# 02_Power_Control.net
KiCad netlist of a schematic drawn in Altium Designer
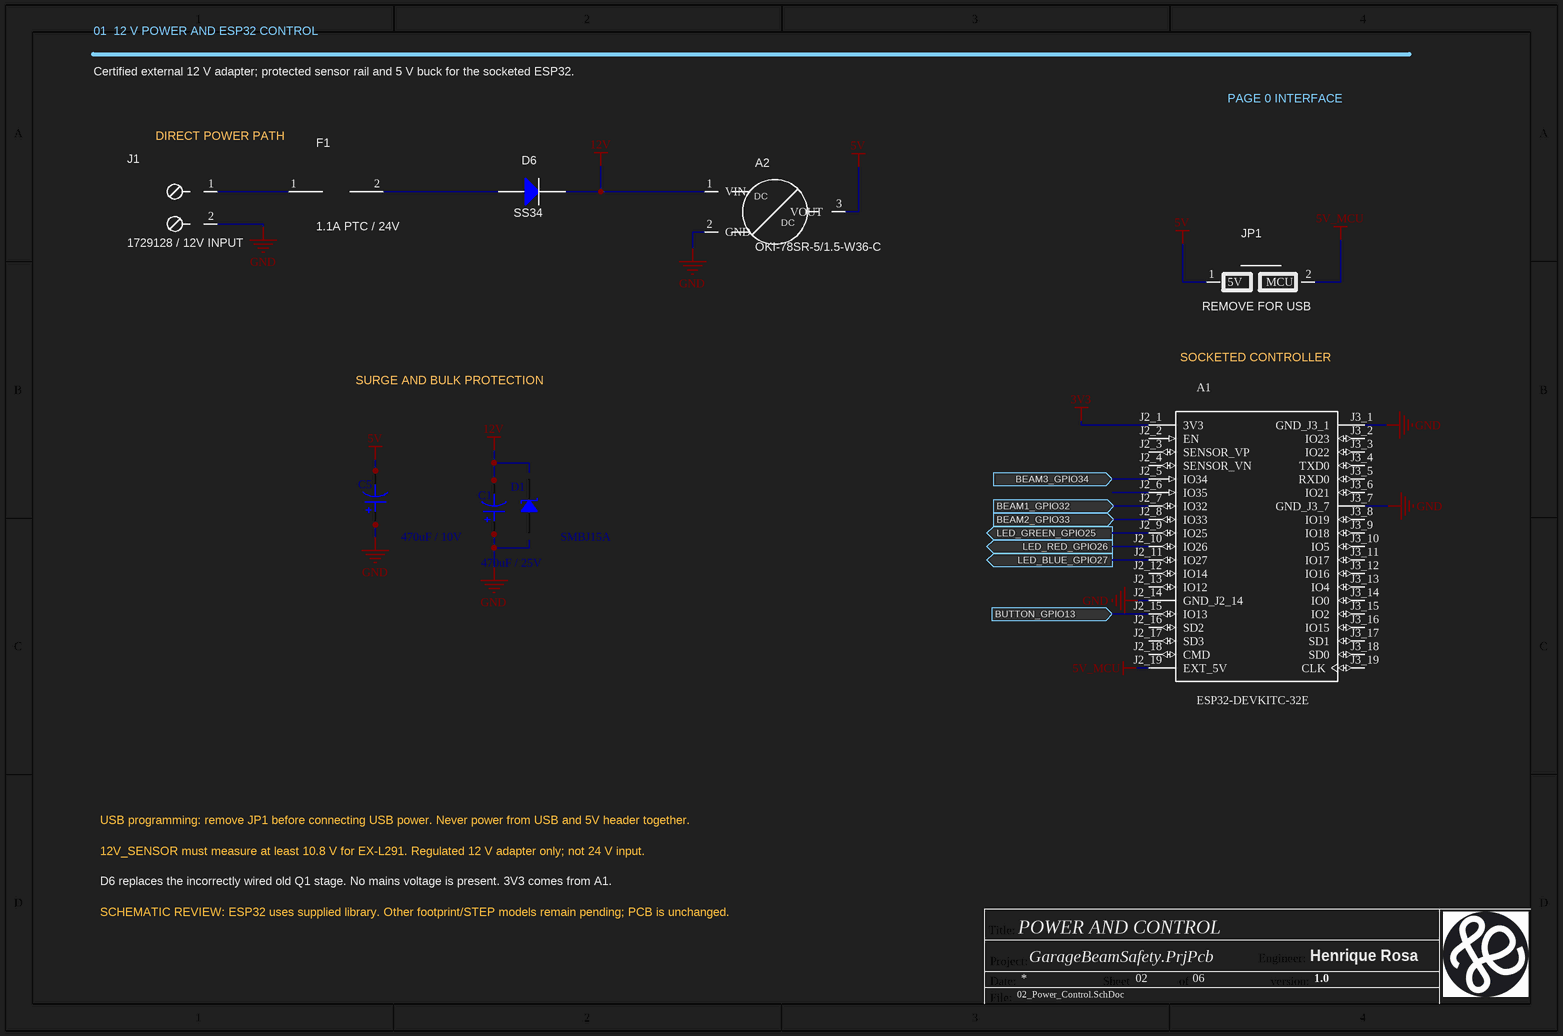
[diagram p0: 02_Power_Control.SchDoc]

(export (version "E")
  (design (tool "Eeschema 10.0.6"))
  (components
    (comp (ref "A1")
      (value "ESP32-DEVKITC-32E")
      (footprint "MODULE_ESP32-DEVKITC-32E:MODULE_ESP32-DEVKITC-32E")
      (fields
        (field (name "MF") "Espressif Systems")
        (field (name "MANUFACTURER PART NUMBER") "ESP32-DevKitC-32E")
      )
      (libsource (lib "ReviewedComponents_20260912-233454") (part "ESP32-DevKitC-32E__A1_view"))
    )
    (comp (ref "A2")
      (value "OKI-78SR-5/1.5-W36-C")
      (footprint "PartSpecificFootprints:MURATA_OKI78SR_VERTICAL")
      (description "12 V to regulated 5 V DC/DC module")
      (fields (field (name "MANUFACTURER") "Murata"))
      (libsource (lib "ReviewedComponents_20260912-233454") (part "OKI-78SR-5_1_5-W36-C__A2_view"))
    )
    (comp (ref "C1")
      (value "470uF / 25V")
      (footprint "PinRepairFootprints:PANASONIC_EEUFR1E471_D10_P5")
      (description "SMT Polarised Capacitor")
      (fields (field (name "PART NUMBER") "EEU-FR1E471") (field (name "MANUFACTURER") "Panasonic"))
      (libsource (lib "SCH - PASSIVES - POLARISED CAPACITOR") (part "Polarised Capacitor"))
    )
    (comp (ref "C5")
      (value "470uF / 10V")
      (footprint "PinRepairFootprints:PANASONIC_EEUFR1A471_D8_P3_5")
      (description "SMT Polarised Capacitor")
      (fields (field (name "PART NUMBER") "EEU-FR1A471") (field (name "MANUFACTURER") "Panasonic"))
      (libsource (lib "SCH - PASSIVES - POLARISED CAPACITOR") (part "Polarised Capacitor"))
    )
    (comp (ref "D1")
      (value "SMBJ15A")
      (footprint "PinRepairFootprints:SMBJ15A_A1_K2")
      (description "Rectifier Diode")
      (fields (field (name "MANUFACTURER") "Littelfuse"))
      (libsource (lib "SCH - DIODES - DIODE TVS UNI") (part "DIODE TVS UNI"))
    )
    (comp (ref "D6")
      (value "SS34")
      (footprint "PinRepairFootprints:SS34_A1_K2")
      (description "Series reverse-polarity Schottky diode")
      (fields (field (name "PART NUMBER") "SS34-E3/57T") (field (name "MANUFACTURER") "Vishay"))
      (libsource (lib "ReviewedComponents_20260912-233454") (part "SS34-E3_57T__D6_view"))
    )
    (comp (ref "F1")
      (value "1.1A PTC / 24V")
      (footprint "PinRepairFootprints:BOURNS_MFMSMF110_24X_STYLE2")
      (description "Resettable 12 V input fuse")
      (fields
        (field (name "MANUFACTURER") "Bourns")
        (field (name "MANUFACTURER PART NUMBER") "MF-MSMF110/24X-2")
      )
      (libsource (lib "ReviewedComponents_20260912-233454") (part "MF-MSMF110_24X-2__F1_view"))
    )
    (comp (ref "J1")
      (value "1729128 / 12V INPUT")
      (footprint "PartSpecificFootprints:PHOENIX_1729128_MKDSN_2_508")
      (description "Two-position 5.08 mm screw terminal")
      (fields
        (field (name "MANUFACTURER") "Phoenix Contact")
        (field (name "MANUFACTURER PART NUMBER") "1729128")
      )
      (libsource (lib "ReviewedComponents_20260912-233454") (part "1729128__J1_view"))
    )
    (comp (ref "JP1")
      (value "REMOVE FOR USB")
      (footprint "PinRepairFootprints:SAMTEC_TSW102_07_SINGLE")
      (description "External 5 V disconnect; fit shunt only without USB")
      (fields
        (field (name "MANUFACTURER") "Samtec")
        (field (name "MANUFACTURER PART NUMBER") "TSW-102-07-G-S")
      )
      (libsource (lib "ReviewedComponents_20260912-233454") (part "TSW-102-07-G-S__JP1_view"))
    )
  )
  (nets
    (net (code "1") (name "/BEAM1_GPIO32") (class "Default")
      (node (ref "A1") (pin "J2_7") (pinfunction "IO32_J2_7") (pintype "bidirectional"))
    )
    (net (code "2") (name "/BEAM2_GPIO33") (class "Default")
      (node (ref "A1") (pin "J2_8") (pinfunction "IO33_J2_8") (pintype "bidirectional"))
    )
    (net (code "3") (name "/BEAM3_GPIO34") (class "Default")
      (node (ref "A1") (pin "J2_5") (pinfunction "IO34_J2_5") (pintype "input"))
    )
    (net (code "4") (name "/BUTTON_GPIO13") (class "Default")
      (node (ref "A1") (pin "J2_15") (pinfunction "IO13_J2_15") (pintype "bidirectional"))
    )
    (net (code "5") (name "/LED_BLUE_GPIO27") (class "Default")
      (node (ref "A1") (pin "J2_11") (pinfunction "IO27_J2_11") (pintype "bidirectional"))
    )
    (net (code "6") (name "/LED_GREEN_GPIO25") (class "Default")
      (node (ref "A1") (pin "J2_9") (pinfunction "IO25_J2_9") (pintype "bidirectional"))
    )
    (net (code "7") (name "/LED_RED_GPIO26") (class "Default")
      (node (ref "A1") (pin "J2_10") (pinfunction "IO26_J2_10") (pintype "bidirectional"))
    )
    (net (code "8") (name "3V3") (class "Default")
      (node (ref "A1") (pin "J2_1") (pinfunction "3V3_J2_1") (pintype "power_in"))
    )
    (net (code "9") (name "5V") (class "Default")
      (node (ref "A2") (pin "3") (pinfunction "VOUT_3") (pintype "passive"))
      (node (ref "C5") (pin "2") (pinfunction "2_2") (pintype "passive"))
      (node (ref "JP1") (pin "1") (pinfunction "5V_1") (pintype "passive"))
    )
    (net (code "10") (name "5V_MCU") (class "Default")
      (node (ref "A1") (pin "J2_19") (pinfunction "EXT_5V_J2_19") (pintype "power_in"))
      (node (ref "JP1") (pin "2") (pinfunction "MCU_2") (pintype "passive"))
    )
    (net (code "11") (name "12V") (class "Default")
      (node (ref "A2") (pin "1") (pinfunction "VIN_1") (pintype "passive"))
      (node (ref "C1") (pin "2") (pinfunction "2_2") (pintype "passive"))
      (node (ref "D6") (pin "2") (pinfunction "K_2") (pintype "passive"))
    )
    (net (code "12") (name "GND") (class "Default")
      (node (ref "A1") (pin "J2_14") (pinfunction "GND_J2_14_J2_14") (pintype "power_in"))
      (node (ref "A1") (pin "J3_1") (pinfunction "GND_J3_1_J3_1") (pintype "power_in"))
      (node (ref "A1") (pin "J3_7") (pinfunction "GND_J3_7_J3_7") (pintype "power_in"))
      (node (ref "A2") (pin "2") (pinfunction "GND_2") (pintype "passive"))
      (node (ref "C1") (pin "1") (pinfunction "1_1") (pintype "passive"))
      (node (ref "C5") (pin "1") (pinfunction "1_1") (pintype "passive"))
      (node (ref "J1") (pin "2") (pinfunction "0V_2") (pintype "power_in"))
    )
    (net (code "13") (name "Net-(D6-A)") (class "Default")
      (node (ref "D6") (pin "1") (pinfunction "A_1") (pintype "passive"))
      (node (ref "F1") (pin "2") (pintype "passive"))
    )
    (net (code "14") (name "Net-(J1-+12V)") (class "Default")
      (node (ref "F1") (pin "1") (pintype "passive"))
      (node (ref "J1") (pin "1") (pinfunction "+12V_1") (pintype "power_in"))
    )
    (net (code "15") (name "unconnected-(A1-CLK-PadJ3_19)") (class "Default")
      (node (ref "A1") (pin "J3_19") (pinfunction "CLK_J3_19") (pintype "bidirectional"))
    )
    (net (code "16") (name "unconnected-(A1-CMD-PadJ2_18)") (class "Default")
      (node (ref "A1") (pin "J2_18") (pinfunction "CMD_J2_18") (pintype "bidirectional"))
    )
    (net (code "17") (name "unconnected-(A1-EN-PadJ2_2)") (class "Default")
      (node (ref "A1") (pin "J2_2") (pinfunction "EN_J2_2") (pintype "input"))
    )
    (net (code "18") (name "unconnected-(A1-IO0-PadJ3_14)") (class "Default")
      (node (ref "A1") (pin "J3_14") (pinfunction "IO0_J3_14") (pintype "bidirectional"))
    )
    (net (code "19") (name "unconnected-(A1-IO2-PadJ3_15)") (class "Default")
      (node (ref "A1") (pin "J3_15") (pinfunction "IO2_J3_15") (pintype "bidirectional"))
    )
    (net (code "20") (name "unconnected-(A1-IO4-PadJ3_13)") (class "Default")
      (node (ref "A1") (pin "J3_13") (pinfunction "IO4_J3_13") (pintype "bidirectional"))
    )
    (net (code "21") (name "unconnected-(A1-IO5-PadJ3_10)") (class "Default")
      (node (ref "A1") (pin "J3_10") (pinfunction "IO5_J3_10") (pintype "bidirectional"))
    )
    (net (code "22") (name "unconnected-(A1-IO12-PadJ2_13)") (class "Default")
      (node (ref "A1") (pin "J2_13") (pinfunction "IO12_J2_13") (pintype "bidirectional"))
    )
    (net (code "23") (name "unconnected-(A1-IO14-PadJ2_12)") (class "Default")
      (node (ref "A1") (pin "J2_12") (pinfunction "IO14_J2_12") (pintype "bidirectional"))
    )
    (net (code "24") (name "unconnected-(A1-IO15-PadJ3_16)") (class "Default")
      (node (ref "A1") (pin "J3_16") (pinfunction "IO15_J3_16") (pintype "bidirectional"))
    )
    (net (code "25") (name "unconnected-(A1-IO16-PadJ3_12)") (class "Default")
      (node (ref "A1") (pin "J3_12") (pinfunction "IO16_J3_12") (pintype "bidirectional"))
    )
    (net (code "26") (name "unconnected-(A1-IO17-PadJ3_11)") (class "Default")
      (node (ref "A1") (pin "J3_11") (pinfunction "IO17_J3_11") (pintype "bidirectional"))
    )
    (net (code "27") (name "unconnected-(A1-IO18-PadJ3_9)") (class "Default")
      (node (ref "A1") (pin "J3_9") (pinfunction "IO18_J3_9") (pintype "bidirectional"))
    )
    (net (code "28") (name "unconnected-(A1-IO19-PadJ3_8)") (class "Default")
      (node (ref "A1") (pin "J3_8") (pinfunction "IO19_J3_8") (pintype "bidirectional"))
    )
    (net (code "29") (name "unconnected-(A1-IO21-PadJ3_6)") (class "Default")
      (node (ref "A1") (pin "J3_6") (pinfunction "IO21_J3_6") (pintype "bidirectional"))
    )
    (net (code "30") (name "unconnected-(A1-IO22-PadJ3_3)") (class "Default")
      (node (ref "A1") (pin "J3_3") (pinfunction "IO22_J3_3") (pintype "bidirectional"))
    )
    (net (code "31") (name "unconnected-(A1-IO23-PadJ3_2)") (class "Default")
      (node (ref "A1") (pin "J3_2") (pinfunction "IO23_J3_2") (pintype "bidirectional"))
    )
    (net (code "32") (name "unconnected-(A1-IO35-PadJ2_6)") (class "Default")
      (node (ref "A1") (pin "J2_6") (pinfunction "IO35_J2_6") (pintype "input"))
    )
    (net (code "33") (name "unconnected-(A1-RXD0-PadJ3_5)") (class "Default")
      (node (ref "A1") (pin "J3_5") (pinfunction "RXD0_J3_5") (pintype "bidirectional"))
    )
    (net (code "34") (name "unconnected-(A1-SD0-PadJ3_18)") (class "Default")
      (node (ref "A1") (pin "J3_18") (pinfunction "SD0_J3_18") (pintype "bidirectional"))
    )
    (net (code "35") (name "unconnected-(A1-SD1-PadJ3_17)") (class "Default")
      (node (ref "A1") (pin "J3_17") (pinfunction "SD1_J3_17") (pintype "bidirectional"))
    )
    (net (code "36") (name "unconnected-(A1-SD2-PadJ2_16)") (class "Default")
      (node (ref "A1") (pin "J2_16") (pinfunction "SD2_J2_16") (pintype "bidirectional"))
    )
    (net (code "37") (name "unconnected-(A1-SD3-PadJ2_17)") (class "Default")
      (node (ref "A1") (pin "J2_17") (pinfunction "SD3_J2_17") (pintype "bidirectional"))
    )
    (net (code "38") (name "unconnected-(A1-SENSOR_VN-PadJ2_4)") (class "Default")
      (node (ref "A1") (pin "J2_4") (pinfunction "SENSOR_VN_J2_4") (pintype "bidirectional"))
    )
    (net (code "39") (name "unconnected-(A1-SENSOR_VP-PadJ2_3)") (class "Default")
      (node (ref "A1") (pin "J2_3") (pinfunction "SENSOR_VP_J2_3") (pintype "bidirectional"))
    )
    (net (code "40") (name "unconnected-(A1-TXD0-PadJ3_4)") (class "Default")
      (node (ref "A1") (pin "J3_4") (pinfunction "TXD0_J3_4") (pintype "bidirectional"))
    )
    (net (code "41") (name "unconnected-(D1-Pad1)") (class "Default")
      (node (ref "D1") (pin "1") (pinfunction "1_1") (pintype "passive"))
    )
    (net (code "42") (name "unconnected-(D1-Pad2)") (class "Default")
      (node (ref "D1") (pin "2") (pinfunction "2_2") (pintype "passive"))
    )
  )
)
